# GSM_Shut_Down_Signal_Control.net
KiCad netlist of a schematic drawn in Altium Designer
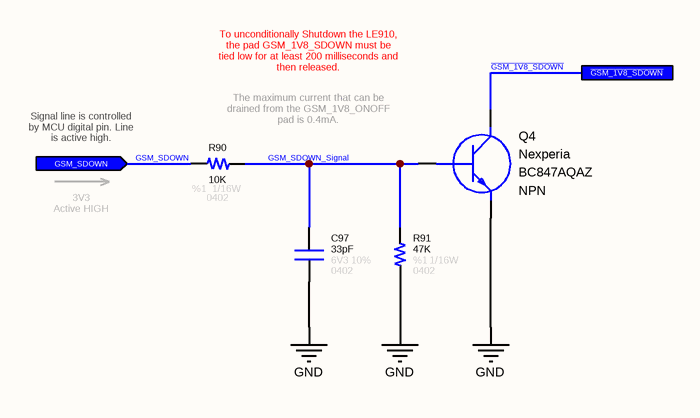
[diagram p0: GSM Shut Down Signal Control.SchDoc]

(export (version "E")
  (design (tool "Eeschema 10.0.6"))
  (components
    (comp (ref "C97")
      (value "33pF")
      (footprint "CAPACITOR_0402")
      (description "Capacitor - 33pF [0402] (Ceramic)")
      (fields
        (field (name "MANUFACTURER PART NUMBER") "C0402C330J9RACAUTO")
        (field (name "TOLERANCE") "10%")
        (field (name "CASE") "0402")
        (field (name "VOLTAGE") "6V3")
      )
      (libsource (lib "Akkoyun") (part "Capacitor - 33pF [0402-6V3]"))
    )
    (comp (ref "Q4")
      (value "BC847AQAZ")
      (footprint "SOT1215")
      (description "Bipolar NPN Transistors")
      (fields
        (field (name "MANUFACTURER NAME") "Nexperia")
        (field (name "MANUFACTURER PART NUMBER") "BC847AQAZ")
        (field (name "POLARITY") "NPN")
      )
      (libsource (lib "Akkoyun") (part "Transistor - BC847"))
    )
    (comp (ref "R90")
      (value "10K")
      (footprint "RESISTOR_0402")
      (description "Thick Film Resistors - SMD 1/16 W 10 KOhm 1%")
      (fields
        (field (name "MANUFACTURER PART NUMBER") "CRCW040210K0FKED")
        (field (name "TOLERANCE") "%1")
        (field (name "CASE") "0402")
        (field (name "POWER") "1/16W")
        (field (name "Comment") "10K - 0402 - %1 - 1/16W")
      )
      (libsource (lib "Akkoyun") (part "Resistor - 10K [0402]"))
    )
    (comp (ref "R91")
      (value "47K")
      (footprint "RESISTOR_0402")
      (description "Thick Film Resistors - SMD 1/16 W 47 KOhm 1%")
      (fields
        (field (name "MANUFACTURER PART NUMBER") "CRCW040247K0FKED")
        (field (name "TOLERANCE") "%1")
        (field (name "CASE") "0402")
        (field (name "POWER") "1/16W")
        (field (name "Comment") "47K - 0402 - %1 - 1/16W")
      )
      (libsource (lib "Akkoyun") (part "Resistor - 47K [0402]"))
    )
  )
  (nets
    (net (code "1") (name "/GSM_SDOWN") (class "Default")
      (node (ref "R90") (pin "2") (pinfunction "2_2") (pintype "passive"))
    )
    (net (code "2") (name "/GSM_SDOWN_Signal") (class "Default")
      (node (ref "C97") (pin "2") (pinfunction "2_2") (pintype "passive"))
      (node (ref "Q4") (pin "1") (pinfunction "B_1") (pintype "passive"))
      (node (ref "R90") (pin "1") (pinfunction "1_1") (pintype "passive"))
      (node (ref "R91") (pin "2") (pinfunction "2_2") (pintype "passive"))
    )
    (net (code "3") (name "/~{GSM_1V8_SDOWN}") (class "Default")
      (node (ref "Q4") (pin "3") (pinfunction "C_3") (pintype "passive"))
    )
    (net (code "4") (name "GND") (class "Default")
      (node (ref "C97") (pin "1") (pinfunction "1_1") (pintype "passive"))
      (node (ref "Q4") (pin "2") (pinfunction "E_2") (pintype "passive"))
      (node (ref "R91") (pin "1") (pinfunction "1_1") (pintype "passive"))
    )
  )
)
